# Sheet1.net
KiCad netlist of a schematic drawn in Altium Designer
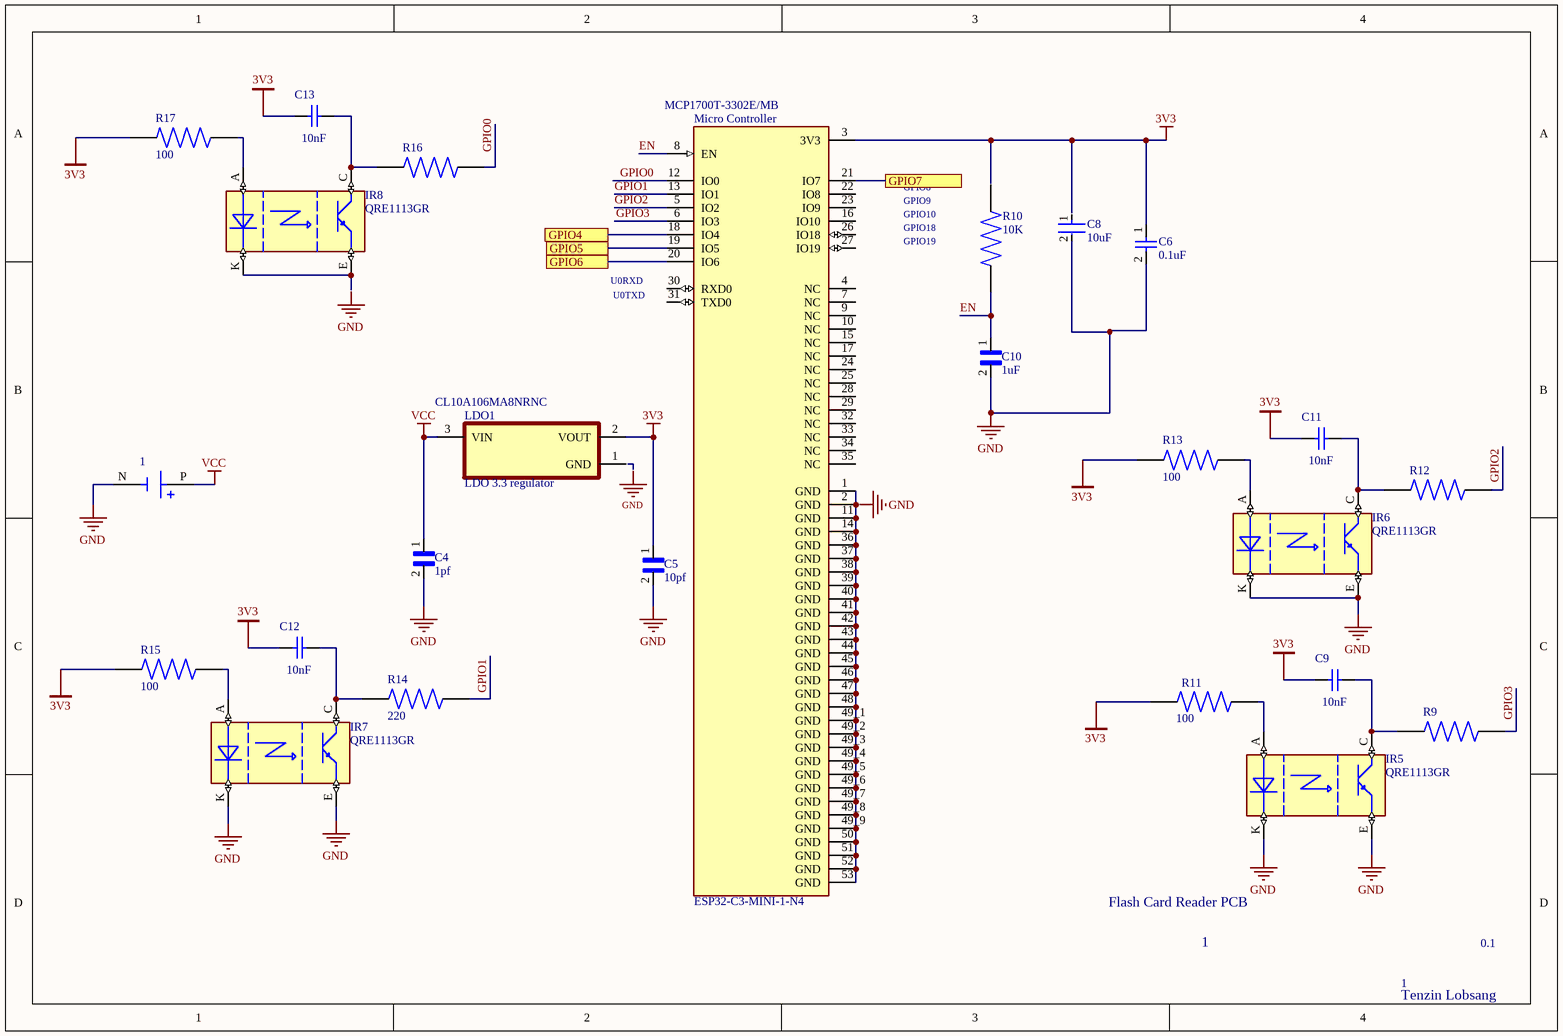
[diagram p0: Sheet1.SchDoc]

(export (version "E")
  (design (tool "Eeschema 10.0.6"))
  (components
    (comp (ref "1")
      (value "~")
      (footprint "BAT_1043")
      (fields (field (name "MP") "1043"))
      (libsource (lib "1043") (part "1043"))
    )
    (comp (ref "C4")
      (value "1pf")
      (footprint "CAPC2012X88N")
      (fields (field (name "MP") "C0805C100K5RAC7800"))
      (libsource (lib "C0805C100K5RAC7800") (part "C0805C100K5RAC7800"))
    )
    (comp (ref "C5")
      (value "10pf")
      (footprint "CAPC2012X88N")
      (fields (field (name "MP") "C0805C100K5RAC7800"))
      (libsource (lib "C0805C100K5RAC7800") (part "C0805C100K5RAC7800"))
    )
    (comp (ref "C6")
      (value "0.1uF")
      (footprint "CAPC1608X90X35NL10T15")
      (description "Chip Capacitor, 0.1 uF, +/- 10%, 50 V, -55 to 125 degC, 0603 (1608 Metric), RoHS, Tape and Reel")
      (fields (field (name "TOLERANCE") "10%") (field (name "VOLTAGE") "50V"))
      (libsource (lib "CAP 0.1uF") (part "CMP-2100-03643-1"))
    )
    (comp (ref "C8")
      (value "10uF")
      (footprint "CAPC2012X88N")
      (description "Cap Ceramic 10uF 25V X5R ±20% Pad SMD 0603 +85°C T/R")
      (fields (field (name "TOLERANCE") "20%"))
      (libsource (lib "CAP 10 uF") (part "CMP-13271-004224-1"))
    )
    (comp (ref "C9")
      (value "10nF")
      (footprint "WCAP-CSGP_0805_L2W1.25H1.25")
      (description "WCAP-CSGP Multilayer Ceramic Chip Capacitor, General Purpose, size 0805, NP0, 10nF, 10V")
      (fields
        (field (name "MANUFACTURER PART NUMBER") "885012007009")
        (field (name "MANUFACTURER") "Wurth Elektronik")
      )
      (libsource (lib "10nf_CAP_WCAP-CSGP") (part "885012007009"))
    )
    (comp (ref "C10")
      (value "1uF")
      (footprint "CAPC1608X90N")
      (description "1ÂµF Â±10% 16V Ceramic Capacitor X7R 0603 (1608 Metric)")
      (fields (field (name "DIGI-KEY_PART_NUMBER") "1276-1019-1-ND") (field (name "MP") "CL10B105KO8NNNC"))
      (libsource (lib "CAP_1uF") (part "CL10B105KO8NNNC"))
    )
    (comp (ref "C11")
      (value "10nF")
      (footprint "WCAP-CSGP_0805_L2W1.25H1.25")
      (description "WCAP-CSGP Multilayer Ceramic Chip Capacitor, General Purpose, size 0805, NP0, 10nF, 10V")
      (fields
        (field (name "MANUFACTURER PART NUMBER") "885012007009")
        (field (name "MANUFACTURER") "Wurth Elektronik")
      )
      (libsource (lib "10nf_CAP_WCAP-CSGP") (part "885012007009"))
    )
    (comp (ref "C12")
      (value "10nF")
      (footprint "WCAP-CSGP_0805_L2W1.25H1.25")
      (description "WCAP-CSGP Multilayer Ceramic Chip Capacitor, General Purpose, size 0805, NP0, 10nF, 10V")
      (fields
        (field (name "MANUFACTURER PART NUMBER") "885012007009")
        (field (name "MANUFACTURER") "Wurth Elektronik")
      )
      (libsource (lib "10nf_CAP_WCAP-CSGP") (part "885012007009"))
    )
    (comp (ref "C13")
      (value "10nF")
      (footprint "WCAP-CSGP_0805_L2W1.25H1.25")
      (description "WCAP-CSGP Multilayer Ceramic Chip Capacitor, General Purpose, size 0805, NP0, 10nF, 10V")
      (fields
        (field (name "MANUFACTURER PART NUMBER") "885012007009")
        (field (name "MANUFACTURER") "Wurth Elektronik")
      )
      (libsource (lib "10nf_CAP_WCAP-CSGP") (part "885012007009"))
    )
    (comp (ref "IR5")
      (value "QRE1113GR")
      (footprint "4LEADSMD")
      (description "Optical Switches, Reflective, Phototransistor Output Reflective Sensor")
      (fields (field (name "MF") "SparkFun") (field (name "MP") "QRE1113"))
      (libsource (lib "QRE1113GR") (part "QRE1113GR"))
    )
    (comp (ref "IR6")
      (value "QRE1113GR")
      (footprint "4LEADSMD")
      (description "Optical Switches, Reflective, Phototransistor Output Reflective Sensor")
      (fields (field (name "MF") "SparkFun") (field (name "MP") "QRE1113"))
      (libsource (lib "QRE1113GR") (part "QRE1113GR"))
    )
    (comp (ref "IR7")
      (value "QRE1113GR")
      (footprint "4LEADSMD")
      (description "Optical Switches, Reflective, Phototransistor Output Reflective Sensor")
      (fields (field (name "MF") "SparkFun") (field (name "MP") "QRE1113"))
      (libsource (lib "QRE1113GR") (part "QRE1113GR"))
    )
    (comp (ref "IR8")
      (value "QRE1113GR")
      (footprint "4LEADSMD")
      (description "Optical Switches, Reflective, Phototransistor Output Reflective Sensor")
      (fields (field (name "MF") "SparkFun") (field (name "MP") "QRE1113"))
      (libsource (lib "QRE1113GR") (part "QRE1113GR"))
    )
    (comp (ref "LDO1")
      (value "LDO 3.3 regulator")
      (footprint "SOT95P237X112-3N")
      (description "25V 10uF X5R ±20% 0603 Multilayer Ceramic Capacitors MLCC - SMD/SMT ROHS")
      (fields
        (field (name "MP") "MCP1700T-3002E/TT")
        (field (name "MF") "Microchip")
        (field (name "SUPPLIER PART NUMBER 1") "CL10A106MA8NRNC")
      )
      (libsource (lib "Flash_Card_Reader_1") (part "MCP1700T-3002E/TT"))
    )
    (comp (ref "Micro Controller")
      (value "ESP32-C3-MINI-1-N4")
      (footprint "XCVR_ESP32-C3-MINI-1-N4")
      (description "Pwr Sply Func, Voltage Regulator, LDO, SOT-89, PD 1.635W, VO 3.3V, Regline +/-0.75%/V")
      (fields
        (field (name "MF") "Espressif Systems")
        (field (name "SUPPLIER PART NUMBER 1") "MCP1700T-3302E/MB")
        (field (name "MANUFACTURER") "Microchip")
      )
      (libsource (lib "ESP32-C3-MINI-1-N4") (part "ESP32-C3-MINI-1-N4"))
    )
    (comp (ref "R9")
      (value "220")
      (footprint "RESC1005X35N")
      (fields
        (field (name "MF") "TE Connectivity")
        (field (name "MP") "CPF0402B220RE1")
        (field (name "TOLERANCE") ".1%")
      )
      (libsource (lib "220_ohm_CPF0402B220RE1") (part "CPF0402B220RE1"))
    )
    (comp (ref "R10")
      (value "10K")
      (footprint "RESC1005X40N")
      (description "CRG0402 chip resistor,10K 5% 0.063W ¦ TE Connectivity CRG0402J10K/10")
      (fields (field (name "MF") "TE Connectivity") (field (name "MP") "CRG0402J10K/10"))
      (libsource (lib "10K_CRG0402J10K_10") (part "CRG0402J10K/10"))
    )
    (comp (ref "R11")
      (value "100")
      (footprint "RESC6432X75N")
      (description "CRS Series Anti-surge Resistor 2512 Case 100Ohms 2W +/-100ppm/degC ¦ Bourns CRS2512-FX-1000ELF")
      (fields (field (name "MF") "Bourns") (field (name "MP") "CRS2512-FX-1000ELF"))
      (libsource (lib "100ohh") (part "CRS2512-FX-1000ELF"))
    )
    (comp (ref "R12")
      (value "220")
      (footprint "RESC1005X35N")
      (fields
        (field (name "MF") "TE Connectivity")
        (field (name "MP") "CPF0402B220RE1")
        (field (name "TOLERANCE") ".1%")
      )
      (libsource (lib "220_ohm_CPF0402B220RE1") (part "CPF0402B220RE1"))
    )
    (comp (ref "R13")
      (value "100")
      (footprint "RESC6432X75N")
      (description "CRS Series Anti-surge Resistor 2512 Case 100Ohms 2W +/-100ppm/degC ¦ Bourns CRS2512-FX-1000ELF")
      (fields (field (name "MF") "Bourns") (field (name "MP") "CRS2512-FX-1000ELF"))
      (libsource (lib "100ohh") (part "CRS2512-FX-1000ELF"))
    )
    (comp (ref "R14")
      (value "220")
      (footprint "RESC1005X35N")
      (fields
        (field (name "MF") "TE Connectivity")
        (field (name "MP") "CPF0402B220RE1")
        (field (name "TOLERANCE") ".1%")
      )
      (libsource (lib "220_ohm_CPF0402B220RE1") (part "CPF0402B220RE1"))
    )
    (comp (ref "R15")
      (value "100")
      (footprint "RESC6432X75N")
      (description "CRS Series Anti-surge Resistor 2512 Case 100Ohms 2W +/-100ppm/degC ¦ Bourns CRS2512-FX-1000ELF")
      (fields (field (name "MF") "Bourns") (field (name "MP") "CRS2512-FX-1000ELF"))
      (libsource (lib "100ohh") (part "CRS2512-FX-1000ELF"))
    )
    (comp (ref "R16")
      (value "220")
      (footprint "RESC1005X35N")
      (fields
        (field (name "MF") "TE Connectivity")
        (field (name "MP") "CPF0402B220RE1")
        (field (name "TOLERANCE") ".1%")
      )
      (libsource (lib "220_ohm_CPF0402B220RE1") (part "CPF0402B220RE1"))
    )
    (comp (ref "R17")
      (value "100")
      (footprint "RESC6432X75N")
      (description "CRS Series Anti-surge Resistor 2512 Case 100Ohms 2W +/-100ppm/degC ¦ Bourns CRS2512-FX-1000ELF")
      (fields (field (name "MF") "Bourns") (field (name "MP") "CRS2512-FX-1000ELF"))
      (libsource (lib "100ohh") (part "CRS2512-FX-1000ELF"))
    )
  )
  (nets
    (net (code "1") (name "/EN") (class "Default")
      (node (ref "C10") (pin "1") (pinfunction "1_1") (pintype "passive"))
      (node (ref "Micro Controller") (pin "8") (pinfunction "EN_8") (pintype "input"))
      (node (ref "R10") (pin "1") (pinfunction "1_1") (pintype "passive"))
    )
    (net (code "2") (name "/GPIO0") (class "Default")
      (node (ref "Micro Controller") (pin "12") (pinfunction "IO0_12") (pintype "passive"))
      (node (ref "R16") (pin "2") (pinfunction "2_2") (pintype "passive"))
    )
    (net (code "3") (name "/GPIO1") (class "Default")
      (node (ref "Micro Controller") (pin "13") (pinfunction "IO1_13") (pintype "passive"))
      (node (ref "R14") (pin "2") (pinfunction "2_2") (pintype "passive"))
    )
    (net (code "4") (name "/GPIO2") (class "Default")
      (node (ref "Micro Controller") (pin "5") (pinfunction "IO2_5") (pintype "passive"))
      (node (ref "R12") (pin "2") (pinfunction "2_2") (pintype "passive"))
    )
    (net (code "5") (name "/GPIO3") (class "Default")
      (node (ref "Micro Controller") (pin "6") (pinfunction "IO3_6") (pintype "passive"))
      (node (ref "R9") (pin "2") (pinfunction "2_2") (pintype "passive"))
    )
    (net (code "6") (name "/GPIO4") (class "Default")
      (node (ref "Micro Controller") (pin "18") (pinfunction "IO4_18") (pintype "passive"))
    )
    (net (code "7") (name "/GPIO5") (class "Default")
      (node (ref "Micro Controller") (pin "19") (pinfunction "IO5_19") (pintype "passive"))
    )
    (net (code "8") (name "/GPIO6") (class "Default")
      (node (ref "Micro Controller") (pin "20") (pinfunction "IO6_20") (pintype "passive"))
    )
    (net (code "9") (name "/GPIO7") (class "Default")
      (node (ref "Micro Controller") (pin "21") (pinfunction "IO7_21") (pintype "passive"))
    )
    (net (code "10") (name "3V3") (class "Default")
      (node (ref "C11") (pin "1") (pinfunction "1_1") (pintype "passive"))
      (node (ref "C12") (pin "1") (pinfunction "1_1") (pintype "passive"))
      (node (ref "C13") (pin "1") (pinfunction "1_1") (pintype "passive"))
      (node (ref "C5") (pin "1") (pinfunction "1_1") (pintype "passive"))
      (node (ref "C6") (pin "1") (pinfunction "1_1") (pintype "passive"))
      (node (ref "C9") (pin "1") (pinfunction "1_1") (pintype "passive"))
      (node (ref "LDO1") (pin "2") (pinfunction "VOUT_2") (pintype "power_in"))
      (node (ref "Micro Controller") (pin "3") (pinfunction "3V3_3") (pintype "power_in"))
      (node (ref "R11") (pin "1") (pinfunction "1_1") (pintype "passive"))
      (node (ref "R13") (pin "1") (pinfunction "1_1") (pintype "passive"))
      (node (ref "R15") (pin "1") (pinfunction "1_1") (pintype "passive"))
      (node (ref "R17") (pin "1") (pinfunction "1_1") (pintype "passive"))
    )
    (net (code "11") (name "GND") (class "Default")
      (node (ref "1") (pin "N") (pinfunction "NEG_N") (pintype "passive"))
      (node (ref "C10") (pin "2") (pinfunction "2_2") (pintype "passive"))
      (node (ref "C4") (pin "2") (pinfunction "2_2") (pintype "passive"))
      (node (ref "C5") (pin "2") (pinfunction "2_2") (pintype "passive"))
      (node (ref "C6") (pin "2") (pinfunction "2_2") (pintype "passive"))
      (node (ref "C8") (pin "2") (pinfunction "2_2") (pintype "passive"))
      (node (ref "IR5") (pin "E") (pinfunction "E_E") (pintype "bidirectional"))
      (node (ref "IR5") (pin "K") (pinfunction "K_K") (pintype "bidirectional"))
      (node (ref "IR6") (pin "E") (pinfunction "E_E") (pintype "bidirectional"))
      (node (ref "IR6") (pin "K") (pinfunction "K_K") (pintype "bidirectional"))
      (node (ref "IR7") (pin "E") (pinfunction "E_E") (pintype "bidirectional"))
      (node (ref "IR7") (pin "K") (pinfunction "K_K") (pintype "bidirectional"))
    )
    (net (code "12") (name "Net-(C9-Pad2)") (class "Default")
      (node (ref "C9") (pin "2") (pinfunction "2_2") (pintype "passive"))
      (node (ref "IR5") (pin "C") (pinfunction "C_C") (pintype "bidirectional"))
      (node (ref "R9") (pin "1") (pinfunction "1_1") (pintype "passive"))
    )
    (net (code "13") (name "Net-(C11-Pad2)") (class "Default")
      (node (ref "C11") (pin "2") (pinfunction "2_2") (pintype "passive"))
      (node (ref "IR6") (pin "C") (pinfunction "C_C") (pintype "bidirectional"))
      (node (ref "R12") (pin "1") (pinfunction "1_1") (pintype "passive"))
    )
    (net (code "14") (name "Net-(C12-Pad2)") (class "Default")
      (node (ref "C12") (pin "2") (pinfunction "2_2") (pintype "passive"))
      (node (ref "IR7") (pin "C") (pinfunction "C_C") (pintype "bidirectional"))
      (node (ref "R14") (pin "1") (pinfunction "1_1") (pintype "passive"))
    )
    (net (code "15") (name "Net-(C13-Pad2)") (class "Default")
      (node (ref "C13") (pin "2") (pinfunction "2_2") (pintype "passive"))
      (node (ref "IR8") (pin "C") (pinfunction "C_C") (pintype "bidirectional"))
      (node (ref "R16") (pin "1") (pinfunction "1_1") (pintype "passive"))
    )
    (net (code "16") (name "Net-(IR5-PadA)") (class "Default")
      (node (ref "IR5") (pin "A") (pinfunction "A_A") (pintype "bidirectional"))
      (node (ref "R11") (pin "2") (pinfunction "2_2") (pintype "passive"))
    )
    (net (code "17") (name "Net-(IR6-PadA)") (class "Default")
      (node (ref "IR6") (pin "A") (pinfunction "A_A") (pintype "bidirectional"))
      (node (ref "R13") (pin "2") (pinfunction "2_2") (pintype "passive"))
    )
    (net (code "18") (name "Net-(IR7-PadA)") (class "Default")
      (node (ref "IR7") (pin "A") (pinfunction "A_A") (pintype "bidirectional"))
      (node (ref "R15") (pin "2") (pinfunction "2_2") (pintype "passive"))
    )
    (net (code "19") (name "Net-(IR8-PadA)") (class "Default")
      (node (ref "IR8") (pin "A") (pinfunction "A_A") (pintype "bidirectional"))
      (node (ref "R17") (pin "2") (pinfunction "2_2") (pintype "passive"))
    )
    (net (code "20") (name "Net-(IR8-PadE)") (class "Default")
      (node (ref "IR8") (pin "E") (pinfunction "E_E") (pintype "bidirectional"))
      (node (ref "IR8") (pin "K") (pinfunction "K_K") (pintype "bidirectional"))
    )
    (net (code "21") (name "Net-(Micro Controller-GND-Pad1)") (class "Default")
      (node (ref "Micro Controller") (pin "1") (pinfunction "GND_1") (pintype "power_in"))
      (node (ref "Micro Controller") (pin "11") (pinfunction "GND_11") (pintype "power_in"))
      (node (ref "Micro Controller") (pin "14") (pinfunction "GND_14") (pintype "power_in"))
      (node (ref "Micro Controller") (pin "2") (pinfunction "GND_2") (pintype "power_in"))
      (node (ref "Micro Controller") (pin "36") (pinfunction "GND_36") (pintype "power_in"))
      (node (ref "Micro Controller") (pin "37") (pinfunction "GND_37") (pintype "power_in"))
      (node (ref "Micro Controller") (pin "38") (pinfunction "GND_38") (pintype "power_in"))
      (node (ref "Micro Controller") (pin "39") (pinfunction "GND_39") (pintype "power_in"))
      (node (ref "Micro Controller") (pin "40") (pinfunction "GND_40") (pintype "power_in"))
      (node (ref "Micro Controller") (pin "41") (pinfunction "GND_41") (pintype "power_in"))
      (node (ref "Micro Controller") (pin "42") (pinfunction "GND_42") (pintype "power_in"))
      (node (ref "Micro Controller") (pin "43") (pinfunction "GND_43") (pintype "power_in"))
      (node (ref "Micro Controller") (pin "44") (pinfunction "GND_44") (pintype "power_in"))
      (node (ref "Micro Controller") (pin "45") (pinfunction "GND_45") (pintype "power_in"))
      (node (ref "Micro Controller") (pin "46") (pinfunction "GND_46") (pintype "power_in"))
      (node (ref "Micro Controller") (pin "47") (pinfunction "GND_47") (pintype "power_in"))
      (node (ref "Micro Controller") (pin "48") (pinfunction "GND_48") (pintype "power_in"))
      (node (ref "Micro Controller") (pin "49_1") (pinfunction "GND_49_1") (pintype "power_in"))
      (node (ref "Micro Controller") (pin "49_2") (pinfunction "GND_49_2") (pintype "power_in"))
      (node (ref "Micro Controller") (pin "49_3") (pinfunction "GND_49_3") (pintype "power_in"))
      (node (ref "Micro Controller") (pin "49_4") (pinfunction "GND_49_4") (pintype "power_in"))
      (node (ref "Micro Controller") (pin "49_5") (pinfunction "GND_49_5") (pintype "power_in"))
      (node (ref "Micro Controller") (pin "49_6") (pinfunction "GND_49_6") (pintype "power_in"))
      (node (ref "Micro Controller") (pin "49_7") (pinfunction "GND_49_7") (pintype "power_in"))
      (node (ref "Micro Controller") (pin "49_8") (pinfunction "GND_49_8") (pintype "power_in"))
      (node (ref "Micro Controller") (pin "49_9") (pinfunction "GND_49_9") (pintype "power_in"))
      (node (ref "Micro Controller") (pin "50") (pinfunction "GND_50") (pintype "power_in"))
      (node (ref "Micro Controller") (pin "51") (pinfunction "GND_51") (pintype "power_in"))
      (node (ref "Micro Controller") (pin "52") (pinfunction "GND_52") (pintype "power_in"))
      (node (ref "Micro Controller") (pin "53") (pinfunction "GND_53") (pintype "power_in"))
    )
    (net (code "22") (name "VCC") (class "Default")
      (node (ref "1") (pin "P") (pinfunction "POS_P") (pintype "passive"))
      (node (ref "C4") (pin "1") (pinfunction "1_1") (pintype "passive"))
      (node (ref "LDO1") (pin "3") (pinfunction "VIN_3") (pintype "power_in"))
    )
    (net (code "23") (name "unconnected-(C8-Pad1)") (class "Default")
      (node (ref "C8") (pin "1") (pinfunction "1_1") (pintype "passive"))
    )
    (net (code "24") (name "unconnected-(LDO1-GND-Pad1)") (class "Default")
      (node (ref "LDO1") (pin "1") (pinfunction "GND_1") (pintype "power_in"))
    )
    (net (code "25") (name "unconnected-(Micro Controller-IO8-Pad22)") (class "Default")
      (node (ref "Micro Controller") (pin "22") (pinfunction "IO8_22") (pintype "passive"))
    )
    (net (code "26") (name "unconnected-(Micro Controller-IO9-Pad23)") (class "Default")
      (node (ref "Micro Controller") (pin "23") (pinfunction "IO9_23") (pintype "passive"))
    )
    (net (code "27") (name "unconnected-(Micro Controller-IO10-Pad16)") (class "Default")
      (node (ref "Micro Controller") (pin "16") (pinfunction "IO10_16") (pintype "passive"))
    )
    (net (code "28") (name "unconnected-(Micro Controller-IO18-Pad26)") (class "Default")
      (node (ref "Micro Controller") (pin "26") (pinfunction "IO18_26") (pintype "bidirectional"))
    )
    (net (code "29") (name "unconnected-(Micro Controller-IO19-Pad27)") (class "Default")
      (node (ref "Micro Controller") (pin "27") (pinfunction "IO19_27") (pintype "bidirectional"))
    )
    (net (code "30") (name "unconnected-(Micro Controller-NC-Pad4)") (class "Default")
      (node (ref "Micro Controller") (pin "4") (pinfunction "NC_4") (pintype "passive"))
    )
    (net (code "31") (name "unconnected-(Micro Controller-NC-Pad7)") (class "Default")
      (node (ref "Micro Controller") (pin "7") (pinfunction "NC_7") (pintype "passive"))
    )
    (net (code "32") (name "unconnected-(Micro Controller-NC-Pad9)") (class "Default")
      (node (ref "Micro Controller") (pin "9") (pinfunction "NC_9") (pintype "passive"))
    )
    (net (code "33") (name "unconnected-(Micro Controller-NC-Pad10)") (class "Default")
      (node (ref "Micro Controller") (pin "10") (pinfunction "NC_10") (pintype "passive"))
    )
    (net (code "34") (name "unconnected-(Micro Controller-NC-Pad15)") (class "Default")
      (node (ref "Micro Controller") (pin "15") (pinfunction "NC_15") (pintype "passive"))
    )
    (net (code "35") (name "unconnected-(Micro Controller-NC-Pad17)") (class "Default")
      (node (ref "Micro Controller") (pin "17") (pinfunction "NC_17") (pintype "passive"))
    )
    (net (code "36") (name "unconnected-(Micro Controller-NC-Pad24)") (class "Default")
      (node (ref "Micro Controller") (pin "24") (pinfunction "NC_24") (pintype "passive"))
    )
    (net (code "37") (name "unconnected-(Micro Controller-NC-Pad25)") (class "Default")
      (node (ref "Micro Controller") (pin "25") (pinfunction "NC_25") (pintype "passive"))
    )
    (net (code "38") (name "unconnected-(Micro Controller-NC-Pad28)") (class "Default")
      (node (ref "Micro Controller") (pin "28") (pinfunction "NC_28") (pintype "passive"))
    )
    (net (code "39") (name "unconnected-(Micro Controller-NC-Pad29)") (class "Default")
      (node (ref "Micro Controller") (pin "29") (pinfunction "NC_29") (pintype "passive"))
    )
    (net (code "40") (name "unconnected-(Micro Controller-NC-Pad32)") (class "Default")
      (node (ref "Micro Controller") (pin "32") (pinfunction "NC_32") (pintype "passive"))
    )
    (net (code "41") (name "unconnected-(Micro Controller-NC-Pad33)") (class "Default")
      (node (ref "Micro Controller") (pin "33") (pinfunction "NC_33") (pintype "passive"))
    )
    (net (code "42") (name "unconnected-(Micro Controller-NC-Pad34)") (class "Default")
      (node (ref "Micro Controller") (pin "34") (pinfunction "NC_34") (pintype "passive"))
    )
    (net (code "43") (name "unconnected-(Micro Controller-NC-Pad35)") (class "Default")
      (node (ref "Micro Controller") (pin "35") (pinfunction "NC_35") (pintype "passive"))
    )
    (net (code "44") (name "unconnected-(Micro Controller-RXD0-Pad30)") (class "Default")
      (node (ref "Micro Controller") (pin "30") (pinfunction "RXD0_30") (pintype "bidirectional"))
    )
    (net (code "45") (name "unconnected-(Micro Controller-TXD0-Pad31)") (class "Default")
      (node (ref "Micro Controller") (pin "31") (pinfunction "TXD0_31") (pintype "bidirectional"))
    )
    (net (code "46") (name "unconnected-(R10-Pad2)") (class "Default")
      (node (ref "R10") (pin "2") (pinfunction "2_2") (pintype "passive"))
    )
  )
)
